# headers.net
KiCad netlist of a schematic drawn in Altium Designer
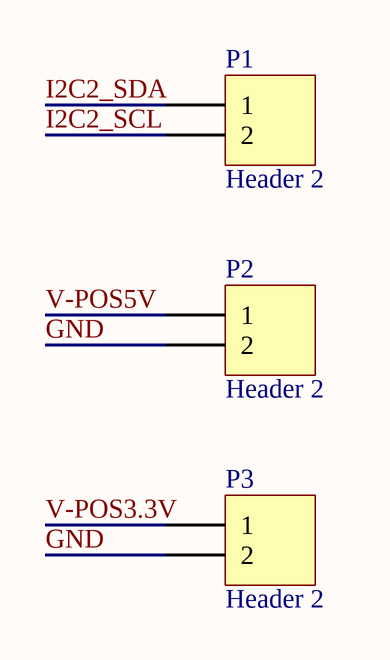
[diagram p0: headers.SchDoc]

(export (version "E")
  (design (tool "Eeschema 10.0.6"))
  (components
    (comp (ref "P1")
      (value "Header 2")
      (footprint "Pin Header 1x2 TH Pitch 2.54mm")
      (description "Header, 2-Pin")
      (fields (field (name "PUBLISHER") "Altium Limited"))
      (libsource (lib "firmware_tutorial_board") (part "Header 2"))
    )
    (comp (ref "P2")
      (value "Header 2")
      (footprint "Pin Header 1x2 TH Pitch 2.54mm")
      (description "Header, 2-Pin")
      (fields (field (name "PUBLISHER") "Altium Limited"))
      (libsource (lib "firmware_tutorial_board") (part "Header 2"))
    )
    (comp (ref "P3")
      (value "Header 2")
      (footprint "Pin Header 1x2 TH Pitch 2.54mm")
      (description "Header, 2-Pin")
      (fields (field (name "PUBLISHER") "Altium Limited"))
      (libsource (lib "firmware_tutorial_board") (part "Header 2"))
    )
  )
  (nets
    (net (code "1") (name "/GND") (class "Default")
      (node (ref "P2") (pin "2") (pinfunction "2_2") (pintype "passive"))
      (node (ref "P3") (pin "2") (pinfunction "2_2") (pintype "passive"))
    )
    (net (code "2") (name "/I2C2_SCL") (class "Default")
      (node (ref "P1") (pin "2") (pinfunction "2_2") (pintype "passive"))
    )
    (net (code "3") (name "/I2C2_SDA") (class "Default")
      (node (ref "P1") (pin "1") (pinfunction "1_1") (pintype "passive"))
    )
    (net (code "4") (name "/V-POS3.3V") (class "Default")
      (node (ref "P3") (pin "1") (pinfunction "1_1") (pintype "passive"))
    )
    (net (code "5") (name "/V-POS5V") (class "Default")
      (node (ref "P2") (pin "1") (pinfunction "1_1") (pintype "passive"))
    )
  )
)
